# Accumulator.net
KiCad netlist of a schematic drawn in Altium Designer
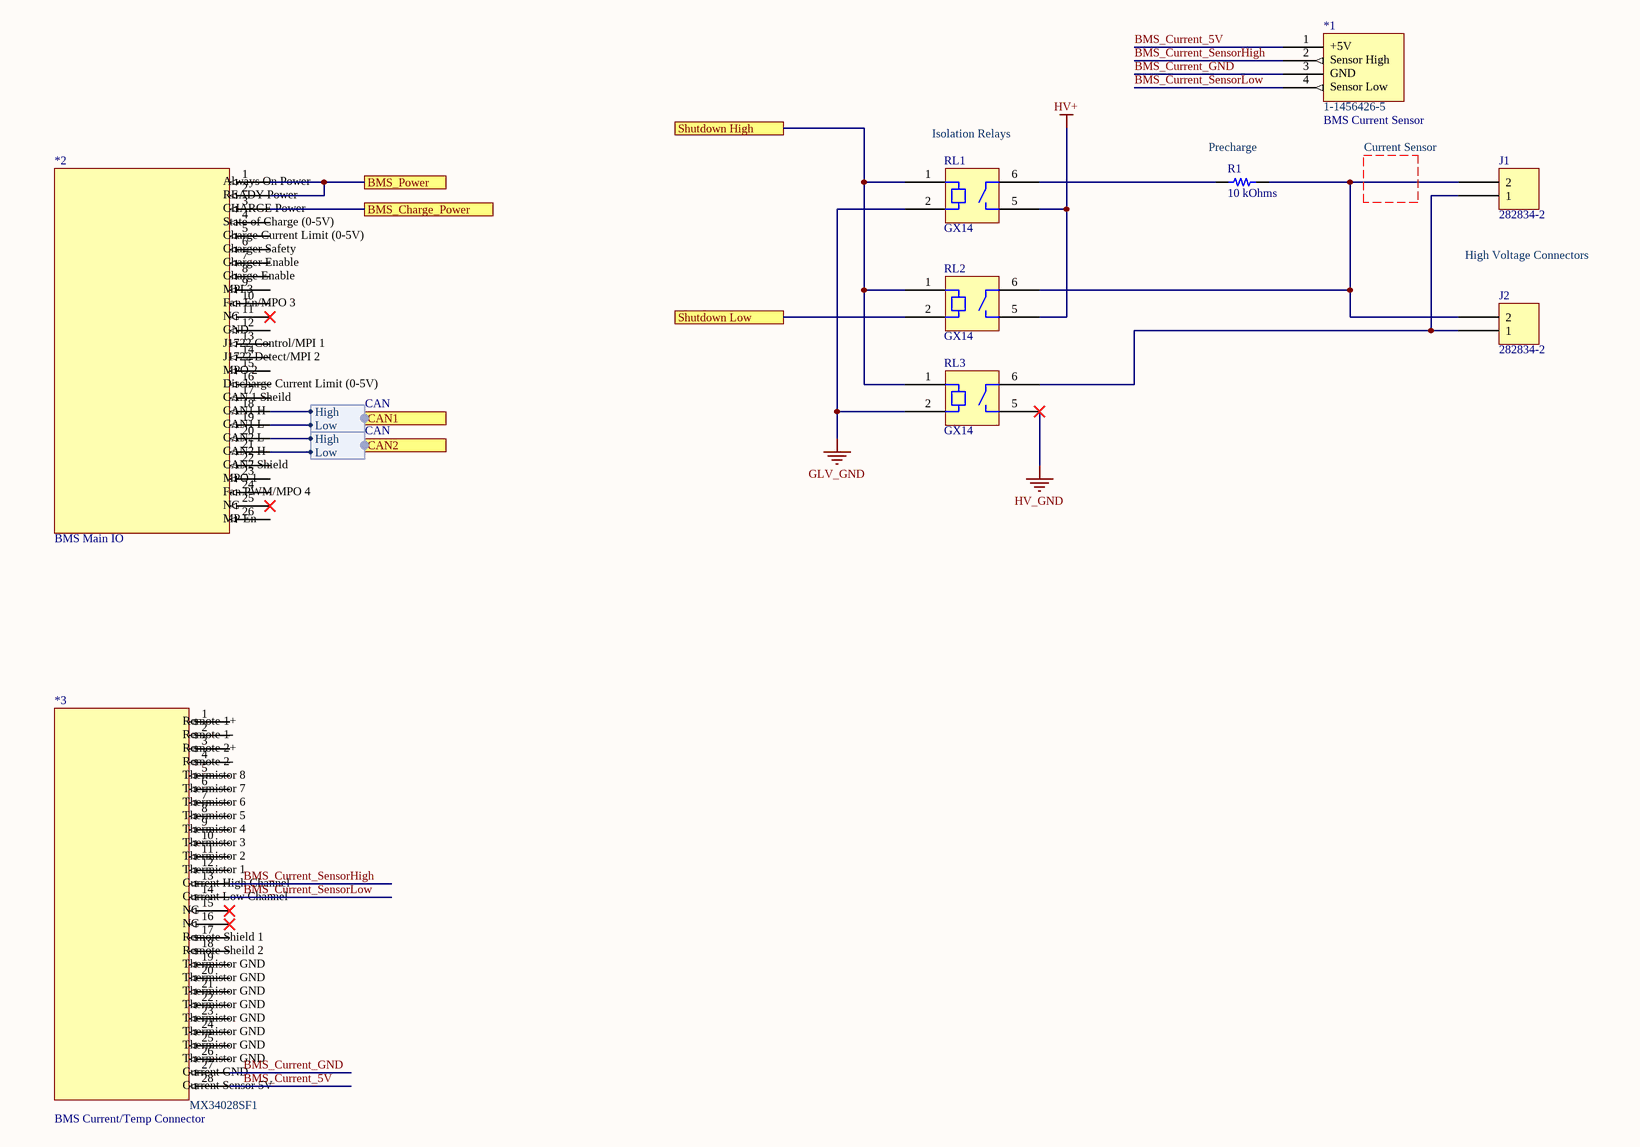
[diagram p0: Accumulator.SchDoc]

(export (version "E")
  (design (tool "Eeschema 10.0.6"))
  (components
    (comp (ref "*1")
      (value "BMS Current Sensor")
      (description "1-1456426-5  Combination Line Connector, 4 Contact(s), Female, Receptacle")
      (libsource (lib "Queens University - FSAE") (part "BMS Current Sensor-Symbol-1"))
    )
    (comp (ref "*2")
      (value "BMS Main IO")
      (description "1376360-1 Combination Line Connector, 26 Contact(s), Female, Crimp Terminal, Plug")
      (libsource (lib "Queens University - FSAE") (part "1376360-1-Symbol-1"))
    )
    (comp (ref "*3")
      (value "BMS Current/Temp Connector")
      (description "Combination Line Connector, 28 Contact(s), Female")
      (libsource (lib "Queens University - FSAE") (part "MX34028SF1-Symbol-1"))
    )
    (comp (ref "J1")
      (value "282834-2")
      (footprint "TE 282834-2")
      (description "TERM BLK 2P SIDE ENT 2.54MM PCB")
      (fields (field (name "MANUFACTURER") "TE Connectivity AMP Connectors") (field (name "VOLTAGE") "150V"))
      (libsource (lib "Celestial Altium Library - altium_library") (part "2 Pin"))
    )
    (comp (ref "J2")
      (value "282834-2")
      (footprint "TE 282834-2")
      (description "TERM BLK 2P SIDE ENT 2.54MM PCB")
      (fields (field (name "MANUFACTURER") "TE Connectivity AMP Connectors") (field (name "VOLTAGE") "150V"))
      (libsource (lib "Celestial Altium Library - altium_library") (part "2 Pin"))
    )
    (comp (ref "R1")
      (value "10 kOhms")
      (footprint "RES 0603_1608")
      (description "1/16 WATTS PRECISION CHIP 10 KIL")
      (fields (field (name "PART NUMBER") "APC0603B10K0N") (field (name "MANUFACTURER") "Ohmite"))
      (libsource (lib "Celestial Altium Library - altium_library") (part "Resistor"))
    )
    (comp (ref "RL1")
      (value "GX14")
      (footprint "PANASONIC APAN31nn PA-N")
      (description "RELAY GENERAL PURPOSE SPST 5A 5V")
      (fields
        (field (name "PART NUMBER") "APAN3105")
        (field (name "MANUFACTURER") "Panasonic Electric Works")
      )
      (libsource (lib "Celestial Altium Library - altium_library") (part "PANASONIC APAN31NN PA-N"))
    )
    (comp (ref "RL2")
      (value "GX14")
      (footprint "PANASONIC APAN31nn PA-N")
      (description "RELAY GENERAL PURPOSE SPST 5A 5V")
      (fields
        (field (name "PART NUMBER") "APAN3105")
        (field (name "MANUFACTURER") "Panasonic Electric Works")
      )
      (libsource (lib "Celestial Altium Library - altium_library") (part "PANASONIC APAN31NN PA-N"))
    )
    (comp (ref "RL3")
      (value "GX14")
      (footprint "PANASONIC APAN31nn PA-N")
      (description "RELAY GENERAL PURPOSE SPST 5A 5V")
      (fields
        (field (name "PART NUMBER") "APAN3105")
        (field (name "MANUFACTURER") "Panasonic Electric Works")
      )
      (libsource (lib "Celestial Altium Library - altium_library") (part "PANASONIC APAN31NN PA-N"))
    )
  )
  (nets
    (net (code "2") (name "/BMS_Charge_Power") (class "Default")
      (node (ref "*2") (pin "3") (pintype "input"))
    )
    (net (code "3") (name "/BMS_Current_5V") (class "Default")
      (node (ref "*1") (pin "1") (pintype "passive"))
      (node (ref "*3") (pin "28") (pintype "input"))
    )
    (net (code "4") (name "/BMS_Current_GND") (class "Default")
      (node (ref "*1") (pin "3") (pintype "passive"))
      (node (ref "*3") (pin "27") (pintype "input"))
    )
    (net (code "5") (name "/BMS_Current_SensorHigh") (class "Default")
      (node (ref "*1") (pin "2") (pintype "output"))
      (node (ref "*3") (pin "13") (pintype "input"))
    )
    (net (code "6") (name "/BMS_Current_SensorLow") (class "Default")
      (node (ref "*1") (pin "4") (pintype "output"))
      (node (ref "*3") (pin "14") (pintype "input"))
    )
    (net (code "7") (name "/BMS_Power") (class "Default")
      (node (ref "*2") (pin "1") (pintype "input"))
      (node (ref "*2") (pin "2") (pintype "input"))
    )
    (net (code "8") (name "/Shutdown High") (class "Default")
      (node (ref "RL1") (pin "1") (pinfunction "COIL1_1") (pintype "passive"))
      (node (ref "RL2") (pin "1") (pinfunction "COIL1_1") (pintype "passive"))
      (node (ref "RL3") (pin "1") (pinfunction "COIL1_1") (pintype "passive"))
    )
    (net (code "9") (name "/Shutdown Low") (class "Default")
      (node (ref "RL2") (pin "2") (pinfunction "COIL2_2") (pintype "passive"))
    )
    (net (code "11") (name "GLV_GND") (class "Default")
      (node (ref "RL1") (pin "2") (pinfunction "COIL2_2") (pintype "passive"))
      (node (ref "RL3") (pin "2") (pinfunction "COIL2_2") (pintype "passive"))
    )
    (net (code "12") (name "HV+") (class "Default")
      (node (ref "RL1") (pin "5") (pinfunction "TERM1_5") (pintype "passive"))
      (node (ref "RL2") (pin "5") (pinfunction "TERM1_5") (pintype "passive"))
    )
    (net (code "13") (name "HV_GND") (class "Default")
      (node (ref "RL3") (pin "5") (pinfunction "TERM1_5") (pintype "passive"))
    )
    (net (code "14") (name "Net-(RL1-TERM2)") (class "Default")
      (node (ref "R1") (pin "2") (pinfunction "2_2") (pintype "passive"))
      (node (ref "RL1") (pin "6") (pinfunction "TERM2_6") (pintype "passive"))
    )
    (net (code "15") (name "Net-(RL2-TERM2)") (class "Default")
      (node (ref "J1") (pin "2") (pinfunction "2_2") (pintype "passive"))
      (node (ref "J2") (pin "2") (pinfunction "2_2") (pintype "passive"))
      (node (ref "R1") (pin "1") (pinfunction "1_1") (pintype "passive"))
      (node (ref "RL2") (pin "6") (pinfunction "TERM2_6") (pintype "passive"))
    )
    (net (code "16") (name "Net-(RL3-TERM2)") (class "Default")
      (node (ref "J1") (pin "1") (pinfunction "1_1") (pintype "passive"))
      (node (ref "J2") (pin "1") (pinfunction "1_1") (pintype "passive"))
      (node (ref "RL3") (pin "6") (pinfunction "TERM2_6") (pintype "passive"))
    )
    (net (code "17") (name "unconnected-(*2-Pad4)") (class "Default")
      (node (ref "*2") (pin "4") (pintype "input"))
    )
    (net (code "18") (name "unconnected-(*2-Pad5)") (class "Default")
      (node (ref "*2") (pin "5") (pintype "input"))
    )
    (net (code "19") (name "unconnected-(*2-Pad6)") (class "Default")
      (node (ref "*2") (pin "6") (pintype "input"))
    )
    (net (code "20") (name "unconnected-(*2-Pad7)") (class "Default")
      (node (ref "*2") (pin "7") (pintype "input"))
    )
    (net (code "21") (name "unconnected-(*2-Pad8)") (class "Default")
      (node (ref "*2") (pin "8") (pintype "input"))
    )
    (net (code "22") (name "unconnected-(*2-Pad9)") (class "Default")
      (node (ref "*2") (pin "9") (pintype "input"))
    )
    (net (code "23") (name "unconnected-(*2-Pad10)") (class "Default")
      (node (ref "*2") (pin "10") (pintype "input"))
    )
    (net (code "24") (name "unconnected-(*2-Pad11)") (class "Default")
      (node (ref "*2") (pin "11") (pintype "input+no_connect"))
    )
    (net (code "25") (name "unconnected-(*2-Pad12)") (class "Default")
      (node (ref "*2") (pin "12") (pintype "input"))
    )
    (net (code "26") (name "unconnected-(*2-Pad13)") (class "Default")
      (node (ref "*2") (pin "13") (pintype "input"))
    )
    (net (code "27") (name "unconnected-(*2-Pad14)") (class "Default")
      (node (ref "*2") (pin "14") (pintype "input"))
    )
    (net (code "28") (name "unconnected-(*2-Pad15)") (class "Default")
      (node (ref "*2") (pin "15") (pintype "input"))
    )
    (net (code "29") (name "unconnected-(*2-Pad16)") (class "Default")
      (node (ref "*2") (pin "16") (pintype "input"))
    )
    (net (code "30") (name "unconnected-(*2-Pad17)") (class "Default")
      (node (ref "*2") (pin "17") (pintype "input"))
    )
    (net (code "31") (name "unconnected-(*2-Pad18)") (class "Default")
      (node (ref "*2") (pin "18") (pintype "input"))
    )
    (net (code "32") (name "unconnected-(*2-Pad19)") (class "Default")
      (node (ref "*2") (pin "19") (pintype "input"))
    )
    (net (code "33") (name "unconnected-(*2-Pad20)") (class "Default")
      (node (ref "*2") (pin "20") (pintype "input"))
    )
    (net (code "34") (name "unconnected-(*2-Pad21)") (class "Default")
      (node (ref "*2") (pin "21") (pintype "input"))
    )
    (net (code "35") (name "unconnected-(*2-Pad22)") (class "Default")
      (node (ref "*2") (pin "22") (pintype "input"))
    )
    (net (code "36") (name "unconnected-(*2-Pad23)") (class "Default")
      (node (ref "*2") (pin "23") (pintype "input"))
    )
    (net (code "37") (name "unconnected-(*2-Pad24)") (class "Default")
      (node (ref "*2") (pin "24") (pintype "input"))
    )
    (net (code "38") (name "unconnected-(*2-Pad25)") (class "Default")
      (node (ref "*2") (pin "25") (pintype "input+no_connect"))
    )
    (net (code "39") (name "unconnected-(*2-Pad26)") (class "Default")
      (node (ref "*2") (pin "26") (pintype "input"))
    )
    (net (code "40") (name "unconnected-(*3-Pad1)") (class "Default")
      (node (ref "*3") (pin "1") (pintype "input"))
    )
    (net (code "41") (name "unconnected-(*3-Pad2)") (class "Default")
      (node (ref "*3") (pin "2") (pintype "input"))
    )
    (net (code "42") (name "unconnected-(*3-Pad3)") (class "Default")
      (node (ref "*3") (pin "3") (pintype "input"))
    )
    (net (code "43") (name "unconnected-(*3-Pad4)") (class "Default")
      (node (ref "*3") (pin "4") (pintype "input"))
    )
    (net (code "44") (name "unconnected-(*3-Pad5)") (class "Default")
      (node (ref "*3") (pin "5") (pintype "input"))
    )
    (net (code "45") (name "unconnected-(*3-Pad6)") (class "Default")
      (node (ref "*3") (pin "6") (pintype "input"))
    )
    (net (code "46") (name "unconnected-(*3-Pad7)") (class "Default")
      (node (ref "*3") (pin "7") (pintype "input"))
    )
    (net (code "47") (name "unconnected-(*3-Pad8)") (class "Default")
      (node (ref "*3") (pin "8") (pintype "input"))
    )
    (net (code "48") (name "unconnected-(*3-Pad9)") (class "Default")
      (node (ref "*3") (pin "9") (pintype "input"))
    )
    (net (code "49") (name "unconnected-(*3-Pad10)") (class "Default")
      (node (ref "*3") (pin "10") (pintype "input"))
    )
    (net (code "50") (name "unconnected-(*3-Pad11)") (class "Default")
      (node (ref "*3") (pin "11") (pintype "input"))
    )
    (net (code "51") (name "unconnected-(*3-Pad12)") (class "Default")
      (node (ref "*3") (pin "12") (pintype "input"))
    )
    (net (code "52") (name "unconnected-(*3-Pad15)") (class "Default")
      (node (ref "*3") (pin "15") (pintype "input+no_connect"))
    )
    (net (code "53") (name "unconnected-(*3-Pad16)") (class "Default")
      (node (ref "*3") (pin "16") (pintype "input+no_connect"))
    )
    (net (code "54") (name "unconnected-(*3-Pad17)") (class "Default")
      (node (ref "*3") (pin "17") (pintype "input"))
    )
    (net (code "55") (name "unconnected-(*3-Pad18)") (class "Default")
      (node (ref "*3") (pin "18") (pintype "input"))
    )
    (net (code "56") (name "unconnected-(*3-Pad19)") (class "Default")
      (node (ref "*3") (pin "19") (pintype "input"))
    )
    (net (code "57") (name "unconnected-(*3-Pad20)") (class "Default")
      (node (ref "*3") (pin "20") (pintype "input"))
    )
    (net (code "58") (name "unconnected-(*3-Pad21)") (class "Default")
      (node (ref "*3") (pin "21") (pintype "input"))
    )
    (net (code "59") (name "unconnected-(*3-Pad22)") (class "Default")
      (node (ref "*3") (pin "22") (pintype "input"))
    )
    (net (code "60") (name "unconnected-(*3-Pad23)") (class "Default")
      (node (ref "*3") (pin "23") (pintype "input"))
    )
    (net (code "61") (name "unconnected-(*3-Pad24)") (class "Default")
      (node (ref "*3") (pin "24") (pintype "input"))
    )
    (net (code "62") (name "unconnected-(*3-Pad25)") (class "Default")
      (node (ref "*3") (pin "25") (pintype "input"))
    )
    (net (code "63") (name "unconnected-(*3-Pad26)") (class "Default")
      (node (ref "*3") (pin "26") (pintype "input"))
    )
  )
)
